# Sheet2.net
KiCad netlist of a schematic drawn in Altium Designer
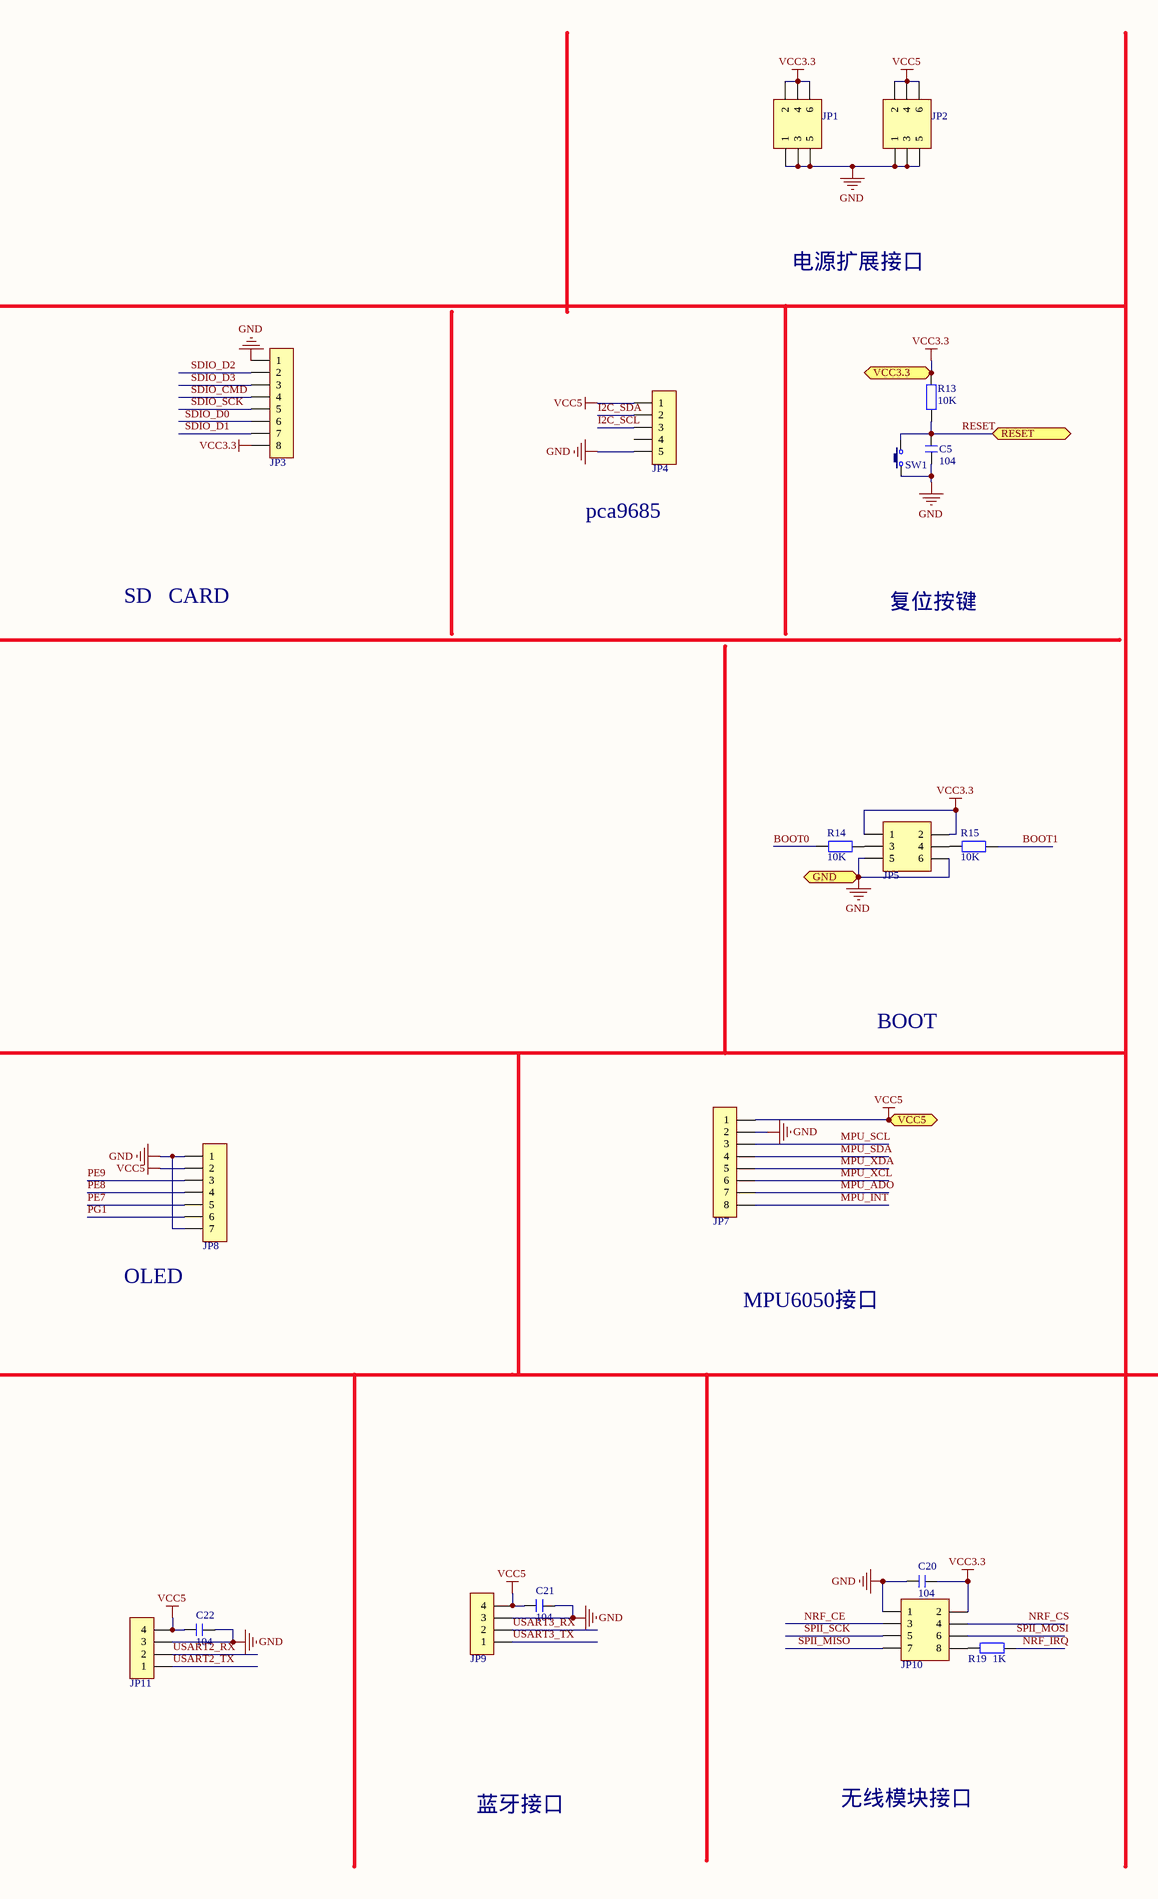
[diagram p0: Sheet2.SchDoc, left]
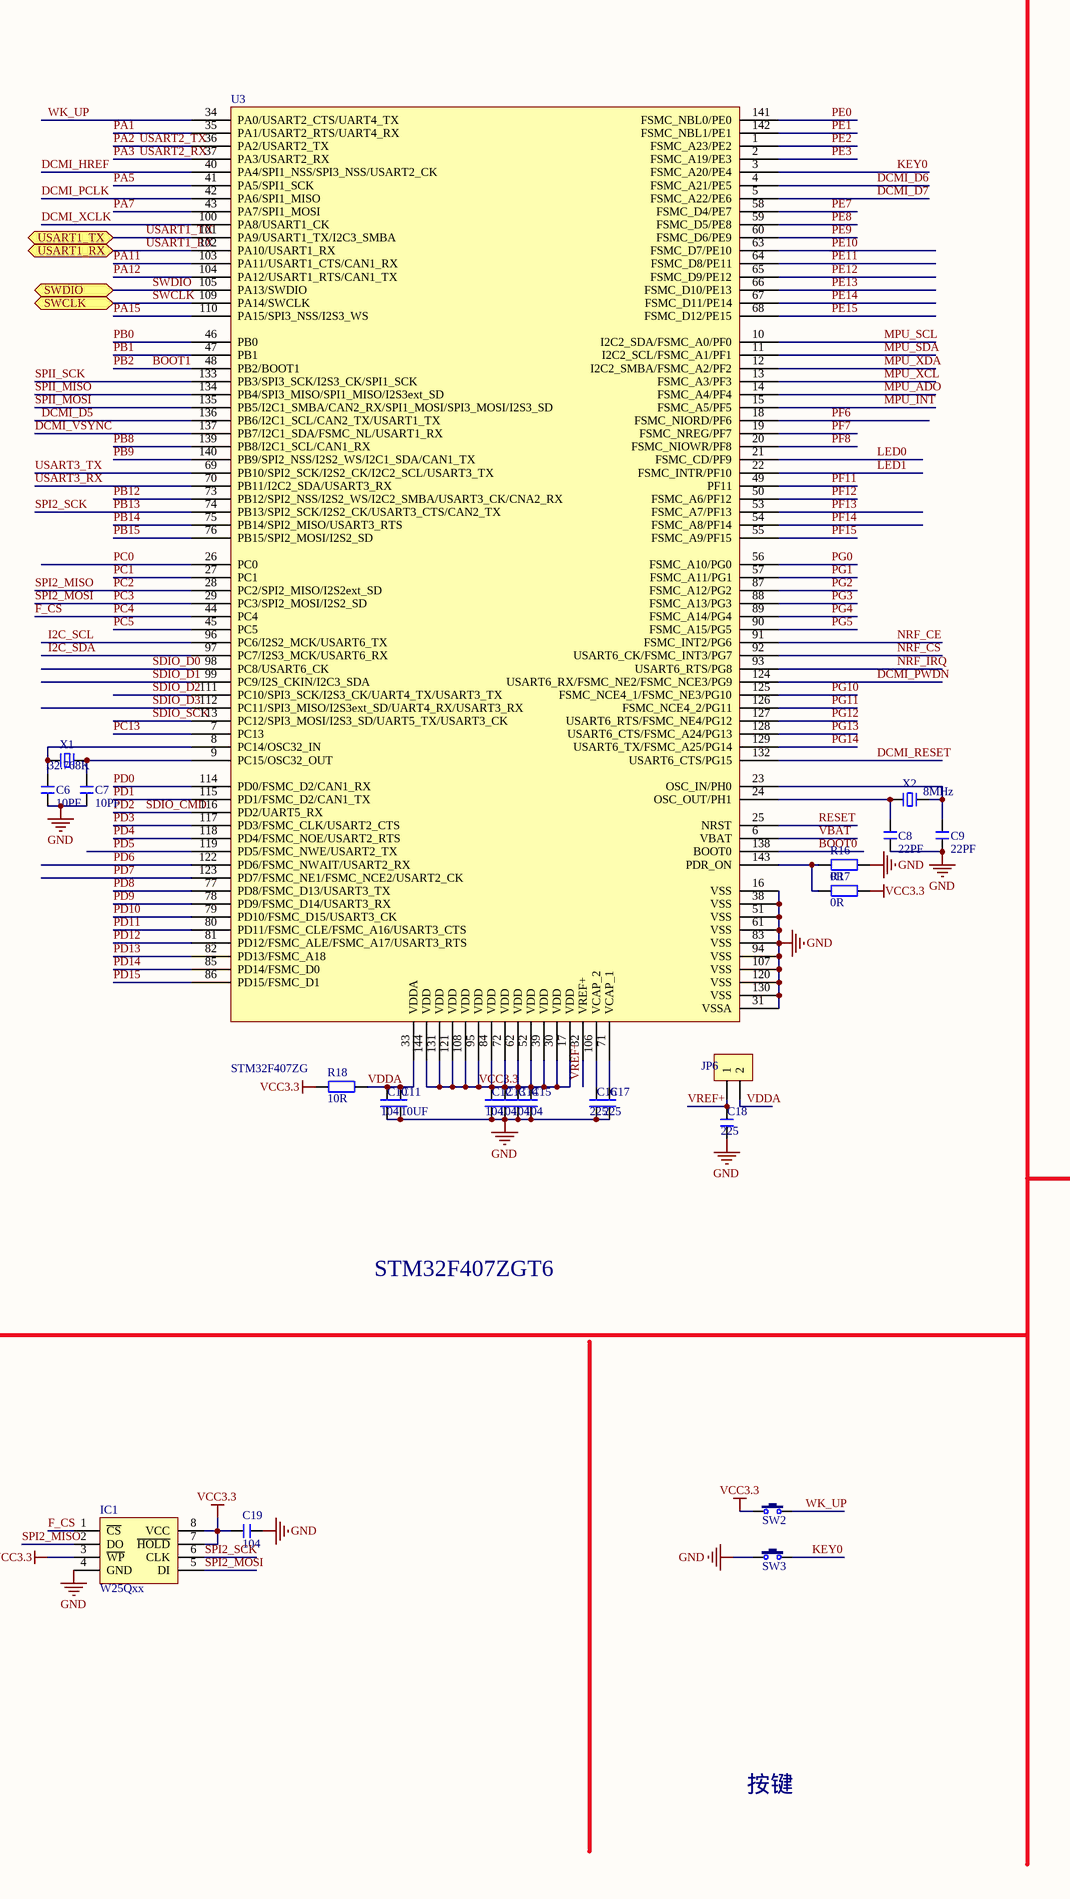
[diagram p1: Sheet2.SchDoc, right]

(export (version "E")
  (design (tool "Eeschema 10.0.6"))
  (components
    (comp (ref "C5")
      (value "104")
      (footprint "C 0603")
      (description "无极性贴片电容")
      (fields (field (name "版权归属") "源创客"))
      (libsource (lib "电阻-电容-电感") (part "C"))
    )
    (comp (ref "C6")
      (value "10PF")
      (footprint "C 0603")
      (description "无极性贴片电容")
      (fields (field (name "版权归属") "源创客"))
      (libsource (lib "电阻-电容-电感") (part "C"))
    )
    (comp (ref "C7")
      (value "10PF")
      (footprint "C 0603")
      (description "无极性贴片电容")
      (fields (field (name "版权归属") "源创客"))
      (libsource (lib "电阻-电容-电感") (part "C"))
    )
    (comp (ref "C8")
      (value "22PF")
      (footprint "C 0603")
      (description "无极性贴片电容")
      (fields (field (name "版权归属") "源创客"))
      (libsource (lib "电阻-电容-电感") (part "C"))
    )
    (comp (ref "C9")
      (value "22PF")
      (footprint "C 0603")
      (description "无极性贴片电容")
      (fields (field (name "版权归属") "源创客"))
      (libsource (lib "电阻-电容-电感") (part "C"))
    )
    (comp (ref "C10")
      (value "104")
      (footprint "C 0603")
      (description "无极性贴片电容")
      (fields (field (name "版权归属") "源创客"))
      (libsource (lib "电阻-电容-电感") (part "C"))
    )
    (comp (ref "C11")
      (value "10UF")
      (footprint "C 0805")
      (description "无极性贴片电容")
      (fields (field (name "版权归属") "源创客"))
      (libsource (lib "电阻-电容-电感") (part "C"))
    )
    (comp (ref "C12")
      (value "104")
      (footprint "C 0603")
      (description "无极性贴片电容")
      (fields (field (name "版权归属") "源创客"))
      (libsource (lib "电阻-电容-电感") (part "C"))
    )
    (comp (ref "C13")
      (value "104")
      (footprint "C 0603")
      (description "无极性贴片电容")
      (fields (field (name "版权归属") "源创客"))
      (libsource (lib "电阻-电容-电感") (part "C"))
    )
    (comp (ref "C14")
      (value "104")
      (footprint "C 0603")
      (description "无极性贴片电容")
      (fields (field (name "版权归属") "源创客"))
      (libsource (lib "电阻-电容-电感") (part "C"))
    )
    (comp (ref "C15")
      (value "104")
      (footprint "C 0603")
      (description "无极性贴片电容")
      (fields (field (name "版权归属") "源创客"))
      (libsource (lib "电阻-电容-电感") (part "C"))
    )
    (comp (ref "C16")
      (value "225")
      (footprint "C 0603")
      (description "无极性贴片电容")
      (fields (field (name "版权归属") "源创客"))
      (libsource (lib "电阻-电容-电感") (part "C"))
    )
    (comp (ref "C17")
      (value "225")
      (footprint "C 0603")
      (description "无极性贴片电容")
      (fields (field (name "版权归属") "源创客"))
      (libsource (lib "电阻-电容-电感") (part "C"))
    )
    (comp (ref "C18")
      (value "225")
      (footprint "C 0603")
      (description "无极性贴片电容")
      (fields (field (name "版权归属") "源创客"))
      (libsource (lib "电阻-电容-电感") (part "C"))
    )
    (comp (ref "C19")
      (value "104")
      (footprint "C 0603")
      (description "无极性贴片电容")
      (fields (field (name "版权归属") "源创客"))
      (libsource (lib "电阻-电容-电感") (part "C"))
    )
    (comp (ref "C20")
      (value "104")
      (footprint "C 0603")
      (description "无极性贴片电容")
      (fields (field (name "版权归属") "源创客"))
      (libsource (lib "电阻-电容-电感") (part "C"))
    )
    (comp (ref "C21")
      (value "104")
      (footprint "C 0603")
      (description "无极性贴片电容")
      (fields (field (name "版权归属") "源创客"))
      (libsource (lib "电阻-电容-电感") (part "C"))
    )
    (comp (ref "C22")
      (value "104")
      (footprint "C 0603")
      (description "无极性贴片电容")
      (fields (field (name "版权归属") "源创客"))
      (libsource (lib "电阻-电容-电感") (part "C"))
    )
    (comp (ref "IC1")
      (value "W25Qxx")
      (footprint "SOP8W_N")
      (description "外置Flash")
      (fields (field (name "版权归属") "黎明电子style"))
      (libsource (lib "IC芯片") (part "W25Qxx"))
    )
    (comp (ref "JP1")
      (value "Header3X2")
      (footprint "HDR-3X2")
      (description "3*2P接插件")
      (fields (field (name "版权归属") "源创客"))
      (libsource (lib "接插件") (part "Header 3X2"))
    )
    (comp (ref "JP2")
      (value "Header3X2")
      (footprint "HDR-3X2")
      (description "3*2P接插件")
      (fields (field (name "版权归属") "源创客"))
      (libsource (lib "接插件") (part "Header 3X2"))
    )
    (comp (ref "JP3")
      (value "HDR-1X8")
      (footprint "HDR-1X8")
      (description "8P接插件")
      (fields (field (name "版权归属") "黎明电子style"))
      (libsource (lib "") (part "Header 8_1"))
    )
    (comp (ref "JP4")
      (value "HDR-1X5")
      (footprint "HDR-1X5")
      (description "5P接插件")
      (fields (field (name "版权归属") "黎明电子style"))
      (libsource (lib "接插件") (part "Header 5"))
    )
    (comp (ref "JP5")
      (value "Header3X2")
      (footprint "HDR-3X2")
      (description "3*2P接插件")
      (fields (field (name "版权归属") "源创客"))
      (libsource (lib "") (part "Header 3X2_1"))
    )
    (comp (ref "JP6")
      (value "HDR-1X2")
      (footprint "HDR-1X2")
      (description "2P接插件")
      (fields (field (name "版权归属") "源创客"))
      (libsource (lib "接插件") (part "Header 2"))
    )
    (comp (ref "JP7")
      (value "HDR-1X8")
      (footprint "HDR-1X8_M")
      (description "8P接插件")
      (fields (field (name "版权归属") "源创客"))
      (libsource (lib "接插件") (part "Header 8"))
    )
    (comp (ref "JP8")
      (value "HDR-1X7")
      (footprint "HDR-1X7")
      (description "7P接插件")
      (fields (field (name "版权归属") "黎明电子style"))
      (libsource (lib "接插件") (part "Header 7"))
    )
    (comp (ref "JP9")
      (value "HDR-1X4")
      (footprint "HDR-1X4_M")
      (description "4P接插件")
      (fields (field (name "版权归属") "源创客"))
      (libsource (lib "接插件") (part "Header 4"))
    )
    (comp (ref "JP10")
      (value "Header 4X2")
      (footprint "HDR-4X2")
      (description "4*2P接插件")
      (fields (field (name "版权归属") "源创客"))
      (libsource (lib "接插件") (part "Header 4X2"))
    )
    (comp (ref "JP11")
      (value "HDR-1X4")
      (footprint "HDR-1X4_M")
      (description "4P接插件")
      (fields (field (name "版权归属") "源创客"))
      (libsource (lib "接插件") (part "Header 4"))
    )
    (comp (ref "R13")
      (value "10K")
      (footprint "R 0603")
      (description "贴片电阻")
      (fields (field (name "版权归属") "源创客"))
      (libsource (lib "电阻-电容-电感") (part "R"))
    )
    (comp (ref "R14")
      (value "10K")
      (footprint "R 0603")
      (description "贴片电阻")
      (fields (field (name "版权归属") "源创客"))
      (libsource (lib "电阻-电容-电感") (part "R"))
    )
    (comp (ref "R15")
      (value "10K")
      (footprint "R 0603")
      (description "贴片电阻")
      (fields (field (name "版权归属") "源创客"))
      (libsource (lib "电阻-电容-电感") (part "R"))
    )
    (comp (ref "R16")
      (value "0R")
      (footprint "R 0603")
      (description "贴片电阻")
      (fields (field (name "版权归属") "源创客"))
      (libsource (lib "电阻-电容-电感") (part "R"))
    )
    (comp (ref "R17")
      (value "0R")
      (footprint "R 0603")
      (description "贴片电阻")
      (fields (field (name "版权归属") "源创客"))
      (libsource (lib "电阻-电容-电感") (part "R"))
    )
    (comp (ref "R18")
      (value "10R")
      (footprint "R 0603")
      (description "贴片电阻")
      (fields (field (name "版权归属") "源创客"))
      (libsource (lib "电阻-电容-电感") (part "R"))
    )
    (comp (ref "R19")
      (value "1K")
      (footprint "R 0603")
      (description "贴片电阻")
      (fields (field (name "版权归属") "源创客"))
      (libsource (lib "电阻-电容-电感") (part "R"))
    )
    (comp (ref "SW1")
      (value "3x6x5")
      (footprint "TSW SMD-3*6*2.5")
      (description "3x6轻触开关")
      (fields (field (name "版权归属") "源创客"))
      (libsource (lib "") (part "TSW 3x6_1"))
    )
    (comp (ref "SW2")
      (value "3x6x5")
      (footprint "TSW SMD-3*6*2.5")
      (description "3x6轻触开关")
      (fields (field (name "版权归属") "源创客"))
      (libsource (lib "按键-开关") (part "TSW 3x6"))
    )
    (comp (ref "SW3")
      (value "3x6x5")
      (footprint "TSW SMD-3*6*2.5")
      (description "3x6轻触开关")
      (fields (field (name "版权归属") "源创客"))
      (libsource (lib "按键-开关") (part "TSW 3x6"))
    )
    (comp (ref "U3")
      (value "STM32F407ZG")
      (footprint "LQFP144 20X20_M")
      (description "Flaah:1024/RAM:192/IO:114")
      (fields (field (name "版权归属") "源创客"))
      (libsource (lib "STM32系列单片机") (part "STM32F407ZG"))
    )
    (comp (ref "X1")
      (value "32.768K")
      (footprint "XTAL-3X8")
      (description "2脚晶振")
      (fields (field (name "版权归属") "源创客"))
      (libsource (lib "保险丝-晶振") (part "XTAL-2"))
    )
    (comp (ref "X2")
      (value "8MHz")
      (footprint "XTAL-49S DIP")
      (description "2脚晶振")
      (fields (field (name "版权归属") "源创客"))
      (libsource (lib "保险丝-晶振") (part "XTAL-2"))
    )
  )
  (nets
    (net (code "1") (name "/BOOT0") (class "Default")
      (node (ref "R14") (pin "2") (pinfunction "2_2") (pintype "passive"))
      (node (ref "U3") (pin "138") (pinfunction "BOOT0_138") (pintype "passive"))
    )
    (net (code "2") (name "/BOOT1") (class "Default")
      (node (ref "R15") (pin "1") (pinfunction "1_1") (pintype "passive"))
      (node (ref "U3") (pin "48") (pinfunction "PB2/BOOT1_48") (pintype "passive"))
    )
    (net (code "3") (name "/DCMI_D5") (class "Default")
      (node (ref "U3") (pin "136") (pinfunction "PB6/I2C1_SCL/CAN2_TX/USART1_TX_136") (pintype "passive"))
    )
    (net (code "4") (name "/DCMI_D6") (class "Default")
      (node (ref "U3") (pin "4") (pinfunction "FSMC_A21/PE5_4") (pintype "passive"))
    )
    (net (code "5") (name "/DCMI_D7") (class "Default")
      (node (ref "U3") (pin "5") (pinfunction "FSMC_A22/PE6_5") (pintype "passive"))
    )
    (net (code "6") (name "/DCMI_HREF") (class "Default")
      (node (ref "U3") (pin "40") (pinfunction "PA4/SPI1_NSS/SPI3_NSS/USART2_CK_40") (pintype "passive"))
    )
    (net (code "7") (name "/DCMI_PCLK") (class "Default")
      (node (ref "U3") (pin "42") (pinfunction "PA6/SPI1_MISO_42") (pintype "passive"))
    )
    (net (code "8") (name "/DCMI_PWDN") (class "Default")
      (node (ref "U3") (pin "124") (pinfunction "USART6_RX/FSMC_NE2/FSMC_NCE3/PG9_124") (pintype "passive"))
    )
    (net (code "9") (name "/DCMI_RESET") (class "Default")
      (node (ref "U3") (pin "132") (pinfunction "USART6_CTS/PG15_132") (pintype "passive"))
    )
    (net (code "10") (name "/DCMI_VSYNC") (class "Default")
      (node (ref "U3") (pin "137") (pinfunction "PB7/I2C1_SDA/FSMC_NL/USART1_RX_137") (pintype "passive"))
    )
    (net (code "11") (name "/DCMI_XCLK") (class "Default")
      (node (ref "U3") (pin "100") (pinfunction "PA8/USART1_CK_100") (pintype "passive"))
    )
    (net (code "12") (name "/F_CS") (class "Default")
      (node (ref "IC1") (pin "1") (pinfunction "~{CS}_1") (pintype "passive"))
      (node (ref "U3") (pin "44") (pinfunction "PC4_44") (pintype "passive"))
    )
    (net (code "13") (name "/I2C_SCL") (class "Default")
      (node (ref "JP4") (pin "3") (pinfunction "3_3") (pintype "passive"))
      (node (ref "U3") (pin "96") (pinfunction "PC6/I2S2_MCK/USART6_TX_96") (pintype "passive"))
    )
    (net (code "14") (name "/I2C_SDA") (class "Default")
      (node (ref "JP4") (pin "2") (pinfunction "2_2") (pintype "passive"))
      (node (ref "U3") (pin "97") (pinfunction "PC7/I2S3_MCK/USART6_RX_97") (pintype "passive"))
    )
    (net (code "15") (name "/KEY0") (class "Default")
      (node (ref "SW3") (pin "2") (pinfunction "2_2") (pintype "passive"))
      (node (ref "U3") (pin "3") (pinfunction "FSMC_A20/PE4_3") (pintype "passive"))
    )
    (net (code "16") (name "/LED0") (class "Default")
      (node (ref "U3") (pin "21") (pinfunction "FSMC_CD/PF9_21") (pintype "passive"))
    )
    (net (code "17") (name "/LED1") (class "Default")
      (node (ref "U3") (pin "22") (pinfunction "FSMC_INTR/PF10_22") (pintype "passive"))
    )
    (net (code "18") (name "/MPU_ADO") (class "Default")
      (node (ref "JP7") (pin "7") (pinfunction "7_7") (pintype "passive"))
      (node (ref "U3") (pin "14") (pinfunction "FSMC_A4/PF4_14") (pintype "passive"))
    )
    (net (code "19") (name "/MPU_INT") (class "Default")
      (node (ref "JP7") (pin "8") (pinfunction "8_8") (pintype "passive"))
      (node (ref "U3") (pin "15") (pinfunction "FSMC_A5/PF5_15") (pintype "passive"))
    )
    (net (code "20") (name "/MPU_SCL") (class "Default")
      (node (ref "JP7") (pin "3") (pinfunction "3_3") (pintype "passive"))
      (node (ref "U3") (pin "10") (pinfunction "I2C2_SDA/FSMC_A0/PF0_10") (pintype "passive"))
    )
    (net (code "21") (name "/MPU_SDA") (class "Default")
      (node (ref "JP7") (pin "4") (pinfunction "4_4") (pintype "passive"))
      (node (ref "U3") (pin "11") (pinfunction "I2C2_SCL/FSMC_A1/PF1_11") (pintype "passive"))
    )
    (net (code "22") (name "/MPU_XCL") (class "Default")
      (node (ref "JP7") (pin "6") (pinfunction "6_6") (pintype "passive"))
      (node (ref "U3") (pin "13") (pinfunction "FSMC_A3/PF3_13") (pintype "passive"))
    )
    (net (code "23") (name "/MPU_XDA") (class "Default")
      (node (ref "JP7") (pin "5") (pinfunction "5_5") (pintype "passive"))
      (node (ref "U3") (pin "12") (pinfunction "I2C2_SMBA/FSMC_A2/PF2_12") (pintype "passive"))
    )
    (net (code "24") (name "/NRF_CE") (class "Default")
      (node (ref "JP10") (pin "3") (pinfunction "3_3") (pintype "passive"))
      (node (ref "U3") (pin "91") (pinfunction "FSMC_INT2/PG6_91") (pintype "passive"))
    )
    (net (code "25") (name "/NRF_CS") (class "Default")
      (node (ref "JP10") (pin "4") (pinfunction "4_4") (pintype "passive"))
      (node (ref "U3") (pin "92") (pinfunction "USART6_CK/FSMC_INT3/PG7_92") (pintype "passive"))
    )
    (net (code "26") (name "/NRF_IRQ") (class "Default")
      (node (ref "R19") (pin "1") (pinfunction "1_1") (pintype "passive"))
      (node (ref "U3") (pin "93") (pinfunction "USART6_RTS/PG8_93") (pintype "passive"))
    )
    (net (code "27") (name "/PA1") (class "Default")
      (node (ref "U3") (pin "35") (pinfunction "PA1/USART2_RTS/UART4_RX_35") (pintype "passive"))
    )
    (net (code "28") (name "/PA2") (class "Default")
      (node (ref "JP11") (pin "1") (pinfunction "1_1") (pintype "passive"))
      (node (ref "U3") (pin "36") (pinfunction "PA2/USART2_TX_36") (pintype "passive"))
    )
    (net (code "29") (name "/PA3") (class "Default")
      (node (ref "JP11") (pin "2") (pinfunction "2_2") (pintype "passive"))
      (node (ref "U3") (pin "37") (pinfunction "PA3/USART2_RX_37") (pintype "passive"))
    )
    (net (code "30") (name "/PA5") (class "Default")
      (node (ref "U3") (pin "41") (pinfunction "PA5/SPI1_SCK_41") (pintype "passive"))
    )
    (net (code "31") (name "/PA7") (class "Default")
      (node (ref "U3") (pin "43") (pinfunction "PA7/SPI1_MOSI_43") (pintype "passive"))
    )
    (net (code "32") (name "/PA11") (class "Default")
      (node (ref "U3") (pin "103") (pinfunction "PA11/USART1_CTS/CAN1_RX_103") (pintype "passive"))
    )
    (net (code "33") (name "/PA12") (class "Default")
      (node (ref "U3") (pin "104") (pinfunction "PA12/USART1_RTS/CAN1_TX_104") (pintype "passive"))
    )
    (net (code "34") (name "/PA15") (class "Default")
      (node (ref "U3") (pin "110") (pinfunction "PA15/SPI3_NSS/I2S3_WS_110") (pintype "passive"))
    )
    (net (code "35") (name "/PB0") (class "Default")
      (node (ref "U3") (pin "46") (pinfunction "PB0_46") (pintype "passive"))
    )
    (net (code "36") (name "/PB1") (class "Default")
      (node (ref "U3") (pin "47") (pinfunction "PB1_47") (pintype "passive"))
    )
    (net (code "37") (name "/PB8") (class "Default")
      (node (ref "U3") (pin "139") (pinfunction "PB8/I2C1_SCL/CAN1_RX_139") (pintype "passive"))
    )
    (net (code "38") (name "/PB9") (class "Default")
      (node (ref "U3") (pin "140") (pinfunction "PB9/SPI2_NSS/I2S2_WS/I2C1_SDA/CAN1_TX_140") (pintype "passive"))
    )
    (net (code "39") (name "/PB12") (class "Default")
      (node (ref "U3") (pin "73") (pinfunction "PB12/SPI2_NSS/I2S2_WS/I2C2_SMBA/USART3_CK/CNA2_RX_73") (pintype "passive"))
    )
    (net (code "40") (name "/PB13") (class "Default")
      (node (ref "IC1") (pin "6") (pinfunction "CLK_6") (pintype "passive"))
      (node (ref "U3") (pin "74") (pinfunction "PB13/SPI2_SCK/I2S2_CK/USART3_CTS/CAN2_TX_74") (pintype "passive"))
    )
    (net (code "41") (name "/PB14") (class "Default")
      (node (ref "U3") (pin "75") (pinfunction "PB14/SPI2_MISO/USART3_RTS_75") (pintype "passive"))
    )
    (net (code "42") (name "/PB15") (class "Default")
      (node (ref "U3") (pin "76") (pinfunction "PB15/SPI2_MOSI/I2S2_SD_76") (pintype "passive"))
    )
    (net (code "43") (name "/PC0") (class "Default")
      (node (ref "U3") (pin "26") (pinfunction "PC0_26") (pintype "passive"))
    )
    (net (code "44") (name "/PC1") (class "Default")
      (node (ref "U3") (pin "27") (pinfunction "PC1_27") (pintype "passive"))
    )
    (net (code "45") (name "/PC2") (class "Default")
      (node (ref "IC1") (pin "2") (pinfunction "DO_2") (pintype "passive"))
      (node (ref "U3") (pin "28") (pinfunction "PC2/SPI2_MISO/I2S2ext_SD_28") (pintype "passive"))
    )
    (net (code "46") (name "/PC3") (class "Default")
      (node (ref "IC1") (pin "5") (pinfunction "DI_5") (pintype "passive"))
      (node (ref "U3") (pin "29") (pinfunction "PC3/SPI2_MOSI/I2S2_SD_29") (pintype "passive"))
    )
    (net (code "47") (name "/PC5") (class "Default")
      (node (ref "U3") (pin "45") (pinfunction "PC5_45") (pintype "passive"))
    )
    (net (code "48") (name "/PC13") (class "Default")
      (node (ref "U3") (pin "7") (pinfunction "PC13_7") (pintype "passive"))
    )
    (net (code "49") (name "/PD0") (class "Default")
      (node (ref "U3") (pin "114") (pinfunction "PD0/FSMC_D2/CAN1_RX_114") (pintype "passive"))
    )
    (net (code "50") (name "/PD1") (class "Default")
      (node (ref "U3") (pin "115") (pinfunction "PD1/FSMC_D2/CAN1_TX_115") (pintype "passive"))
    )
    (net (code "51") (name "/PD2") (class "Default")
      (node (ref "JP3") (pin "4") (pinfunction "4_4") (pintype "passive"))
      (node (ref "U3") (pin "116") (pinfunction "PD2/UART5_RX_116") (pintype "passive"))
    )
    (net (code "52") (name "/PD3") (class "Default")
      (node (ref "U3") (pin "117") (pinfunction "PD3/FSMC_CLK/USART2_CTS_117") (pintype "passive"))
    )
    (net (code "53") (name "/PD4") (class "Default")
      (node (ref "U3") (pin "118") (pinfunction "PD4/FSMC_NOE/USART2_RTS_118") (pintype "passive"))
    )
    (net (code "54") (name "/PD5") (class "Default")
      (node (ref "U3") (pin "119") (pinfunction "PD5/FSMC_NWE/USART2_TX_119") (pintype "passive"))
    )
    (net (code "55") (name "/PD6") (class "Default")
      (node (ref "U3") (pin "122") (pinfunction "PD6/FSMC_NWAIT/USART2_RX_122") (pintype "passive"))
    )
    (net (code "56") (name "/PD7") (class "Default")
      (node (ref "U3") (pin "123") (pinfunction "PD7/FSMC_NE1/FSMC_NCE2/USART2_CK_123") (pintype "passive"))
    )
    (net (code "57") (name "/PD8") (class "Default")
      (node (ref "U3") (pin "77") (pinfunction "PD8/FSMC_D13/USART3_TX_77") (pintype "passive"))
    )
    (net (code "58") (name "/PD9") (class "Default")
      (node (ref "U3") (pin "78") (pinfunction "PD9/FSMC_D14/USART3_RX_78") (pintype "passive"))
    )
    (net (code "59") (name "/PD10") (class "Default")
      (node (ref "U3") (pin "79") (pinfunction "PD10/FSMC_D15/USART3_CK_79") (pintype "passive"))
    )
    (net (code "60") (name "/PD11") (class "Default")
      (node (ref "U3") (pin "80") (pinfunction "PD11/FSMC_CLE/FSMC_A16/USART3_CTS_80") (pintype "passive"))
    )
    (net (code "61") (name "/PD12") (class "Default")
      (node (ref "U3") (pin "81") (pinfunction "PD12/FSMC_ALE/FSMC_A17/USART3_RTS_81") (pintype "passive"))
    )
    (net (code "62") (name "/PD13") (class "Default")
      (node (ref "U3") (pin "82") (pinfunction "PD13/FSMC_A18_82") (pintype "passive"))
    )
    (net (code "63") (name "/PD14") (class "Default")
      (node (ref "U3") (pin "85") (pinfunction "PD14/FSMC_D0_85") (pintype "passive"))
    )
    (net (code "64") (name "/PD15") (class "Default")
      (node (ref "U3") (pin "86") (pinfunction "PD15/FSMC_D1_86") (pintype "passive"))
    )
    (net (code "65") (name "/PE0") (class "Default")
      (node (ref "U3") (pin "141") (pinfunction "FSMC_NBL0/PE0_141") (pintype "passive"))
    )
    (net (code "66") (name "/PE1") (class "Default")
      (node (ref "U3") (pin "142") (pinfunction "FSMC_NBL1/PE1_142") (pintype "passive"))
    )
    (net (code "67") (name "/PE2") (class "Default")
      (node (ref "U3") (pin "1") (pinfunction "FSMC_A23/PE2_1") (pintype "passive"))
    )
    (net (code "68") (name "/PE3") (class "Default")
      (node (ref "U3") (pin "2") (pinfunction "FSMC_A19/PE3_2") (pintype "passive"))
    )
    (net (code "69") (name "/PE7") (class "Default")
      (node (ref "JP8") (pin "5") (pinfunction "5_5") (pintype "passive"))
      (node (ref "U3") (pin "58") (pinfunction "FSMC_D4/PE7_58") (pintype "passive"))
    )
    (net (code "70") (name "/PE8") (class "Default")
      (node (ref "JP8") (pin "4") (pinfunction "4_4") (pintype "passive"))
      (node (ref "U3") (pin "59") (pinfunction "FSMC_D5/PE8_59") (pintype "passive"))
    )
    (net (code "71") (name "/PE9") (class "Default")
      (node (ref "JP8") (pin "3") (pinfunction "3_3") (pintype "passive"))
      (node (ref "U3") (pin "60") (pinfunction "FSMC_D6/PE9_60") (pintype "passive"))
    )
    (net (code "72") (name "/PE10") (class "Default")
      (node (ref "U3") (pin "63") (pinfunction "FSMC_D7/PE10_63") (pintype "passive"))
    )
    (net (code "73") (name "/PE11") (class "Default")
      (node (ref "U3") (pin "64") (pinfunction "FSMC_D8/PE11_64") (pintype "passive"))
    )
    (net (code "74") (name "/PE12") (class "Default")
      (node (ref "U3") (pin "65") (pinfunction "FSMC_D9/PE12_65") (pintype "passive"))
    )
    (net (code "75") (name "/PE13") (class "Default")
      (node (ref "U3") (pin "66") (pinfunction "FSMC_D10/PE13_66") (pintype "passive"))
    )
    (net (code "76") (name "/PE14") (class "Default")
      (node (ref "U3") (pin "67") (pinfunction "FSMC_D11/PE14_67") (pintype "passive"))
    )
    (net (code "77") (name "/PE15") (class "Default")
      (node (ref "U3") (pin "68") (pinfunction "FSMC_D12/PE15_68") (pintype "passive"))
    )
    (net (code "78") (name "/PF6") (class "Default")
      (node (ref "U3") (pin "18") (pinfunction "FSMC_NIORD/PF6_18") (pintype "passive"))
    )
    (net (code "79") (name "/PF7") (class "Default")
      (node (ref "U3") (pin "19") (pinfunction "FSMC_NREG/PF7_19") (pintype "passive"))
    )
    (net (code "80") (name "/PF8") (class "Default")
      (node (ref "U3") (pin "20") (pinfunction "FSMC_NIOWR/PF8_20") (pintype "passive"))
    )
    (net (code "81") (name "/PF11") (class "Default")
      (node (ref "U3") (pin "49") (pinfunction "PF11_49") (pintype "passive"))
    )
    (net (code "82") (name "/PF12") (class "Default")
      (node (ref "U3") (pin "50") (pinfunction "FSMC_A6/PF12_50") (pintype "passive"))
    )
    (net (code "83") (name "/PF13") (class "Default")
      (node (ref "U3") (pin "53") (pinfunction "FSMC_A7/PF13_53") (pintype "passive"))
    )
    (net (code "84") (name "/PF14") (class "Default")
      (node (ref "U3") (pin "54") (pinfunction "FSMC_A8/PF14_54") (pintype "passive"))
    )
    (net (code "85") (name "/PF15") (class "Default")
      (node (ref "U3") (pin "55") (pinfunction "FSMC_A9/PF15_55") (pintype "passive"))
    )
    (net (code "86") (name "/PG0") (class "Default")
      (node (ref "U3") (pin "56") (pinfunction "FSMC_A10/PG0_56") (pintype "passive"))
    )
    (net (code "87") (name "/PG1") (class "Default")
      (node (ref "JP8") (pin "6") (pinfunction "6_6") (pintype "passive"))
      (node (ref "U3") (pin "57") (pinfunction "FSMC_A11/PG1_57") (pintype "passive"))
    )
    (net (code "88") (name "/PG2") (class "Default")
      (node (ref "U3") (pin "87") (pinfunction "FSMC_A12/PG2_87") (pintype "passive"))
    )
    (net (code "89") (name "/PG3") (class "Default")
      (node (ref "U3") (pin "88") (pinfunction "FSMC_A13/PG3_88") (pintype "passive"))
    )
    (net (code "90") (name "/PG4") (class "Default")
      (node (ref "U3") (pin "89") (pinfunction "FSMC_A14/PG4_89") (pintype "passive"))
    )
    (net (code "91") (name "/PG5") (class "Default")
      (node (ref "U3") (pin "90") (pinfunction "FSMC_A15/PG5_90") (pintype "passive"))
    )
    (net (code "92") (name "/PG10") (class "Default")
      (node (ref "U3") (pin "125") (pinfunction "FSMC_NCE4_1/FSMC_NE3/PG10_125") (pintype "passive"))
    )
    (net (code "93") (name "/PG11") (class "Default")
      (node (ref "U3") (pin "126") (pinfunction "FSMC_NCE4_2/PG11_126") (pintype "passive"))
    )
    (net (code "94") (name "/PG12") (class "Default")
      (node (ref "U3") (pin "127") (pinfunction "USART6_RTS/FSMC_NE4/PG12_127") (pintype "passive"))
    )
    (net (code "95") (name "/PG13") (class "Default")
      (node (ref "U3") (pin "128") (pinfunction "USART6_CTS/FSMC_A24/PG13_128") (pintype "passive"))
    )
    (net (code "96") (name "/PG14") (class "Default")
      (node (ref "U3") (pin "129") (pinfunction "USART6_TX/FSMC_A25/PG14_129") (pintype "passive"))
    )
    (net (code "97") (name "/RESET") (class "Default")
      (node (ref "C5") (pin "2") (pinfunction "2_2") (pintype "passive"))
      (node (ref "R13") (pin "1") (pinfunction "1_1") (pintype "passive"))
      (node (ref "SW1") (pin "2") (pinfunction "2_2") (pintype "passive"))
      (node (ref "U3") (pin "25") (pinfunction "NRST_25") (pintype "passive"))
    )
    (net (code "98") (name "/SDIO_D0") (class "Default")
      (node (ref "JP3") (pin "6") (pinfunction "6_6") (pintype "passive"))
      (node (ref "U3") (pin "98") (pinfunction "PC8/USART6_CK_98") (pintype "passive"))
    )
    (net (code "99") (name "/SDIO_D1") (class "Default")
      (node (ref "JP3") (pin "7") (pinfunction "7_7") (pintype "passive"))
      (node (ref "U3") (pin "99") (pinfunction "PC9/I2S_CKIN/I2C3_SDA_99") (pintype "passive"))
    )
    (net (code "100") (name "/SDIO_D2") (class "Default")
      (node (ref "JP3") (pin "2") (pinfunction "2_2") (pintype "passive"))
      (node (ref "U3") (pin "111") (pinfunction "PC10/SPI3_SCK/I2S3_CK/UART4_TX/USART3_TX_111") (pintype "passive"))
    )
    (net (code "101") (name "/SDIO_D3") (class "Default")
      (node (ref "JP3") (pin "3") (pinfunction "3_3") (pintype "passive"))
      (node (ref "U3") (pin "112") (pinfunction "PC11/SPI3_MISO/I2S3ext_SD/UART4_RX/USART3_RX_112") (pintype "passive"))
    )
    (net (code "102") (name "/SDIO_SCK") (class "Default")
      (node (ref "JP3") (pin "5") (pinfunction "5_5") (pintype "passive"))
      (node (ref "U3") (pin "113") (pinfunction "PC12/SPI3_MOSI/I2S3_SD/UART5_TX/USART3_CK_113") (pintype "passive"))
    )
    (net (code "103") (name "/SPII_MISO") (class "Default")
      (node (ref "JP10") (pin "7") (pinfunction "7_7") (pintype "passive"))
      (node (ref "U3") (pin "134") (pinfunction "PB4/SPI3_MISO/SPI1_MISO/I2S3ext_SD_134") (pintype "passive"))
    )
    (net (code "104") (name "/SPII_MOSI") (class "Default")
      (node (ref "JP10") (pin "6") (pinfunction "6_6") (pintype "passive"))
      (node (ref "U3") (pin "135") (pinfunction "PB5/I2C1_SMBA/CAN2_RX/SPI1_MOSI/SPI3_MOSI/I2S3_SD_135") (pintype "passive"))
    )
    (net (code "105") (name "/SPII_SCK") (class "Default")
      (node (ref "JP10") (pin "5") (pinfunction "5_5") (pintype "passive"))
      (node (ref "U3") (pin "133") (pinfunction "PB3/SPI3_SCK/I2S3_CK/SPI1_SCK_133") (pintype "passive"))
    )
    (net (code "106") (name "/SWCLK") (class "Default")
      (node (ref "U3") (pin "109") (pinfunction "PA14/SWCLK_109") (pintype "passive"))
    )
    (net (code "107") (name "/SWDIO") (class "Default")
      (node (ref "U3") (pin "105") (pinfunction "PA13/SWDIO_105") (pintype "passive"))
    )
    (net (code "108") (name "/USART1_RX") (class "Default")
      (node (ref "U3") (pin "102") (pinfunction "PA10/USART1_RX_102") (pintype "passive"))
    )
    (net (code "109") (name "/USART1_TX") (class "Default")
      (node (ref "U3") (pin "101") (pinfunction "PA9/USART1_TX/I2C3_SMBA_101") (pintype "passive"))
    )
    (net (code "110") (name "/USART3_RX") (class "Default")
      (node (ref "JP9") (pin "2") (pinfunction "2_2") (pintype "passive"))
      (node (ref "U3") (pin "70") (pinfunction "PB11/I2C2_SDA/USART3_RX_70") (pintype "passive"))
    )
    (net (code "111") (name "/USART3_TX") (class "Default")
      (node (ref "JP9") (pin "1") (pinfunction "1_1") (pintype "passive"))
      (node (ref "U3") (pin "69") (pinfunction "PB10/SPI2_SCK/I2S2_CK/I2C2_SCL/USART3_TX_69") (pintype "passive"))
    )
    (net (code "112") (name "/VBAT") (class "Default")
      (node (ref "U3") (pin "6") (pinfunction "VBAT_6") (pintype "passive"))
    )
    (net (code "113") (name "/VDDA") (class "Default")
      (node (ref "C10") (pin "2") (pinfunction "2_2") (pintype "passive"))
      (node (ref "C11") (pin "2") (pinfunction "2_2") (pintype "passive"))
      (node (ref "JP6") (pin "2") (pinfunction "2_2") (pintype "passive"))
      (node (ref "R18") (pin "1") (pinfunction "1_1") (pintype "passive"))
      (node (ref "U3") (pin "33") (pinfunction "VDDA_33") (pintype "passive"))
    )
    (net (code "114") (name "/VREF+") (class "Default")
      (node (ref "C18") (pin "2") (pinfunction "2_2") (pintype "passive"))
      (node (ref "JP6") (pin "1") (pinfunction "1_1") (pintype "passive"))
      (node (ref "U3") (pin "32") (pinfunction "VREF+_32") (pintype "passive"))
    )
    (net (code "115") (name "/WK_UP") (class "Default")
      (node (ref "SW2") (pin "2") (pinfunction "2_2") (pintype "passive"))
      (node (ref "U3") (pin "34") (pinfunction "PA0/USART2_CTS/UART4_TX_34") (pintype "passive"))
    )
    (net (code "116") (name "GND") (class "Default")
      (node (ref "C10") (pin "1") (pinfunction "1_1") (pintype "passive"))
      (node (ref "C11") (pin "1") (pinfunction "1_1") (pintype "passive"))
      (node (ref "C12") (pin "1") (pinfunction "1_1") (pintype "passive"))
      (node (ref "C13") (pin "1") (pinfunction "1_1") (pintype "passive"))
      (node (ref "C14") (pin "1") (pinfunction "1_1") (pintype "passive"))
      (node (ref "C15") (pin "1") (pinfunction "1_1") (pintype "passive"))
      (node (ref "C16") (pin "1") (pinfunction "1_1") (pintype "passive"))
      (node (ref "C17") (pin "1") (pinfunction "1_1") (pintype "passive"))
      (node (ref "C18") (pin "1") (pinfunction "1_1") (pintype "passive"))
      (node (ref "C19") (pin "2") (pinfunction "2_2") (pintype "passive"))
      (node (ref "C20") (pin "2") (pinfunction "2_2") (pintype "passive"))
      (node (ref "C21") (pin "1") (pinfunction "1_1") (pintype "passive"))
      (node (ref "C22") (pin "1") (pinfunction "1_1") (pintype "passive"))
      (node (ref "C5") (pin "1") (pinfunction "1_1") (pintype "passive"))
      (node (ref "C6") (pin "1") (pinfunction "1_1") (pintype "passive"))
      (node (ref "C7") (pin "1") (pinfunction "1_1") (pintype "passive"))
      (node (ref "C8") (pin "1") (pinfunction "1_1") (pintype "passive"))
      (node (ref "C9") (pin "1") (pinfunction "1_1") (pintype "passive"))
      (node (ref "IC1") (pin "4") (pinfunction "GND_4") (pintype "passive"))
      (node (ref "JP1") (pin "1") (pinfunction "1_1") (pintype "passive"))
      (node (ref "JP1") (pin "3") (pinfunction "3_3") (pintype "passive"))
      (node (ref "JP1") (pin "5") (pinfunction "5_5") (pintype "passive"))
      (node (ref "JP10") (pin "1") (pinfunction "1_1") (pintype "passive"))
      (node (ref "JP11") (pin "3") (pinfunction "3_3") (pintype "passive"))
      (node (ref "JP2") (pin "1") (pinfunction "1_1") (pintype "passive"))
      (node (ref "JP2") (pin "3") (pinfunction "3_3") (pintype "passive"))
      (node (ref "JP2") (pin "5") (pinfunction "5_5") (pintype "passive"))
      (node (ref "JP3") (pin "1") (pinfunction "1_1") (pintype "passive"))
      (node (ref "JP4") (pin "5") (pinfunction "5_5") (pintype "passive"))
      (node (ref "JP5") (pin "5") (pinfunction "5_5") (pintype "passive"))
      (node (ref "JP5") (pin "6") (pinfunction "6_6") (pintype "passive"))
      (node (ref "JP7") (pin "2") (pinfunction "2_2") (pintype "passive"))
      (node (ref "JP8") (pin "1") (pinfunction "1_1") (pintype "passive"))
      (node (ref "JP8") (pin "7") (pinfunction "7_7") (pintype "passive"))
      (node (ref "JP9") (pin "3") (pinfunction "3_3") (pintype "passive"))
      (node (ref "R16") (pin "1") (pinfunction "1_1") (pintype "passive"))
      (node (ref "SW1") (pin "1") (pinfunction "1_1") (pintype "passive"))
      (node (ref "SW3") (pin "1") (pinfunction "1_1") (pintype "passive"))
      (node (ref "U3") (pin "107") (pinfunction "VSS_107") (pintype "passive"))
      (node (ref "U3") (pin "120") (pinfunction "VSS_120") (pintype "passive"))
      (node (ref "U3") (pin "130") (pinfunction "VSS_130") (pintype "passive"))
      (node (ref "U3") (pin "16") (pinfunction "VSS_16") (pintype "passive"))
      (node (ref "U3") (pin "31") (pinfunction "VSSA_31") (pintype "passive"))
      (node (ref "U3") (pin "38") (pinfunction "VSS_38") (pintype "passive"))
      (node (ref "U3") (pin "51") (pinfunction "VSS_51") (pintype "passive"))
      (node (ref "U3") (pin "61") (pinfunction "VSS_61") (pintype "passive"))
      (node (ref "U3") (pin "83") (pinfunction "VSS_83") (pintype "passive"))
      (node (ref "U3") (pin "94") (pinfunction "VSS_94") (pintype "passive"))
    )
    (net (code "117") (name "Net-(JP5-Pad3)") (class "Default")
      (node (ref "JP5") (pin "3") (pinfunction "3_3") (pintype "passive"))
      (node (ref "R14") (pin "1") (pinfunction "1_1") (pintype "passive"))
    )
    (net (code "118") (name "Net-(JP5-Pad4)") (class "Default")
      (node (ref "JP5") (pin "4") (pinfunction "4_4") (pintype "passive"))
      (node (ref "R15") (pin "2") (pinfunction "2_2") (pintype "passive"))
    )
    (net (code "119") (name "Net-(JP10-Pad8)") (class "Default")
      (node (ref "JP10") (pin "8") (pinfunction "8_8") (pintype "passive"))
      (node (ref "R19") (pin "2") (pinfunction "2_2") (pintype "passive"))
    )
    (net (code "120") (name "Net-(U3-OSC_IN{slash}PH0)") (class "Default")
      (node (ref "C9") (pin "2") (pinfunction "2_2") (pintype "passive"))
      (node (ref "U3") (pin "23") (pinfunction "OSC_IN/PH0_23") (pintype "passive"))
      (node (ref "X2") (pin "2") (pinfunction "2_2") (pintype "passive"))
    )
    (net (code "121") (name "Net-(U3-OSC_OUT{slash}PH1)") (class "Default")
      (node (ref "C8") (pin "2") (pinfunction "2_2") (pintype "passive"))
      (node (ref "U3") (pin "24") (pinfunction "OSC_OUT/PH1_24") (pintype "passive"))
      (node (ref "X2") (pin "1") (pinfunction "1_1") (pintype "passive"))
    )
    (net (code "122") (name "Net-(U3-PC14{slash}OSC32_IN)") (class "Default")
      (node (ref "C6") (pin "2") (pinfunction "2_2") (pintype "passive"))
      (node (ref "U3") (pin "8") (pinfunction "PC14/OSC32_IN_8") (pintype "passive"))
      (node (ref "X1") (pin "1") (pinfunction "1_1") (pintype "passive"))
    )
    (net (code "123") (name "Net-(U3-PC15{slash}OSC32_OUT)") (class "Default")
      (node (ref "C7") (pin "2") (pinfunction "2_2") (pintype "passive"))
      (node (ref "U3") (pin "9") (pinfunction "PC15/OSC32_OUT_9") (pintype "passive"))
      (node (ref "X1") (pin "2") (pinfunction "2_2") (pintype "passive"))
    )
    (net (code "124") (name "Net-(U3-PDR_ON)") (class "Default")
      (node (ref "R16") (pin "2") (pinfunction "2_2") (pintype "passive"))
      (node (ref "R17") (pin "2") (pinfunction "2_2") (pintype "passive"))
      (node (ref "U3") (pin "143") (pinfunction "PDR_ON_143") (pintype "passive"))
    )
    (net (code "125") (name "Net-(U3-VCAP_1)") (class "Default")
      (node (ref "C17") (pin "2") (pinfunction "2_2") (pintype "passive"))
      (node (ref "U3") (pin "71") (pinfunction "VCAP_1_71") (pintype "passive"))
    )
    (net (code "126") (name "Net-(U3-VCAP_2)") (class "Default")
      (node (ref "C16") (pin "2") (pinfunction "2_2") (pintype "passive"))
      (node (ref "U3") (pin "106") (pinfunction "VCAP_2_106") (pintype "passive"))
    )
    (net (code "127") (name "VCC3.3") (class "Default")
      (node (ref "C12") (pin "2") (pinfunction "2_2") (pintype "passive"))
      (node (ref "C13") (pin "2") (pinfunction "2_2") (pintype "passive"))
      (node (ref "C14") (pin "2") (pinfunction "2_2") (pintype "passive"))
      (node (ref "C15") (pin "2") (pinfunction "2_2") (pintype "passive"))
      (node (ref "C19") (pin "1") (pinfunction "1_1") (pintype "passive"))
      (node (ref "C20") (pin "1") (pinfunction "1_1") (pintype "passive"))
      (node (ref "IC1") (pin "3") (pinfunction "~{WP}_3") (pintype "passive"))
      (node (ref "IC1") (pin "7") (pinfunction "~{HOLD}_7") (pintype "passive"))
      (node (ref "IC1") (pin "8") (pinfunction "VCC_8") (pintype "passive"))
      (node (ref "JP1") (pin "2") (pinfunction "2_2") (pintype "passive"))
      (node (ref "JP1") (pin "4") (pinfunction "4_4") (pintype "passive"))
      (node (ref "JP1") (pin "6") (pinfunction "6_6") (pintype "passive"))
      (node (ref "JP10") (pin "2") (pinfunction "2_2") (pintype "passive"))
      (node (ref "JP3") (pin "8") (pinfunction "8_8") (pintype "passive"))
      (node (ref "JP5") (pin "1") (pinfunction "1_1") (pintype "passive"))
      (node (ref "JP5") (pin "2") (pinfunction "2_2") (pintype "passive"))
      (node (ref "R13") (pin "2") (pinfunction "2_2") (pintype "passive"))
      (node (ref "R17") (pin "1") (pinfunction "1_1") (pintype "passive"))
      (node (ref "R18") (pin "2") (pinfunction "2_2") (pintype "passive"))
      (node (ref "SW2") (pin "1") (pinfunction "1_1") (pintype "passive"))
      (node (ref "U3") (pin "108") (pinfunction "VDD_108") (pintype "passive"))
      (node (ref "U3") (pin "121") (pinfunction "VDD_121") (pintype "passive"))
      (node (ref "U3") (pin "131") (pinfunction "VDD_131") (pintype "passive"))
      (node (ref "U3") (pin "144") (pinfunction "VDD_144") (pintype "passive"))
      (node (ref "U3") (pin "17") (pinfunction "VDD_17") (pintype "passive"))
      (node (ref "U3") (pin "30") (pinfunction "VDD_30") (pintype "passive"))
      (node (ref "U3") (pin "39") (pinfunction "VDD_39") (pintype "passive"))
      (node (ref "U3") (pin "52") (pinfunction "VDD_52") (pintype "passive"))
      (node (ref "U3") (pin "62") (pinfunction "VDD_62") (pintype "passive"))
      (node (ref "U3") (pin "72") (pinfunction "VDD_72") (pintype "passive"))
      (node (ref "U3") (pin "84") (pinfunction "VDD_84") (pintype "passive"))
      (node (ref "U3") (pin "95") (pinfunction "VDD_95") (pintype "passive"))
    )
    (net (code "128") (name "VCC5") (class "Default")
      (node (ref "C21") (pin "2") (pinfunction "2_2") (pintype "passive"))
      (node (ref "C22") (pin "2") (pinfunction "2_2") (pintype "passive"))
      (node (ref "JP11") (pin "4") (pinfunction "4_4") (pintype "passive"))
      (node (ref "JP2") (pin "2") (pinfunction "2_2") (pintype "passive"))
      (node (ref "JP2") (pin "4") (pinfunction "4_4") (pintype "passive"))
      (node (ref "JP2") (pin "6") (pinfunction "6_6") (pintype "passive"))
      (node (ref "JP4") (pin "1") (pinfunction "1_1") (pintype "passive"))
      (node (ref "JP7") (pin "1") (pinfunction "1_1") (pintype "passive"))
      (node (ref "JP8") (pin "2") (pinfunction "2_2") (pintype "passive"))
      (node (ref "JP9") (pin "4") (pinfunction "4_4") (pintype "passive"))
    )
    (net (code "129") (name "unconnected-(JP4-Pad4)") (class "Default")
      (node (ref "JP4") (pin "4") (pinfunction "4_4") (pintype "passive"))
    )
  )
)
